# Sheet2.net
KiCad netlist of a schematic drawn in Altium Designer
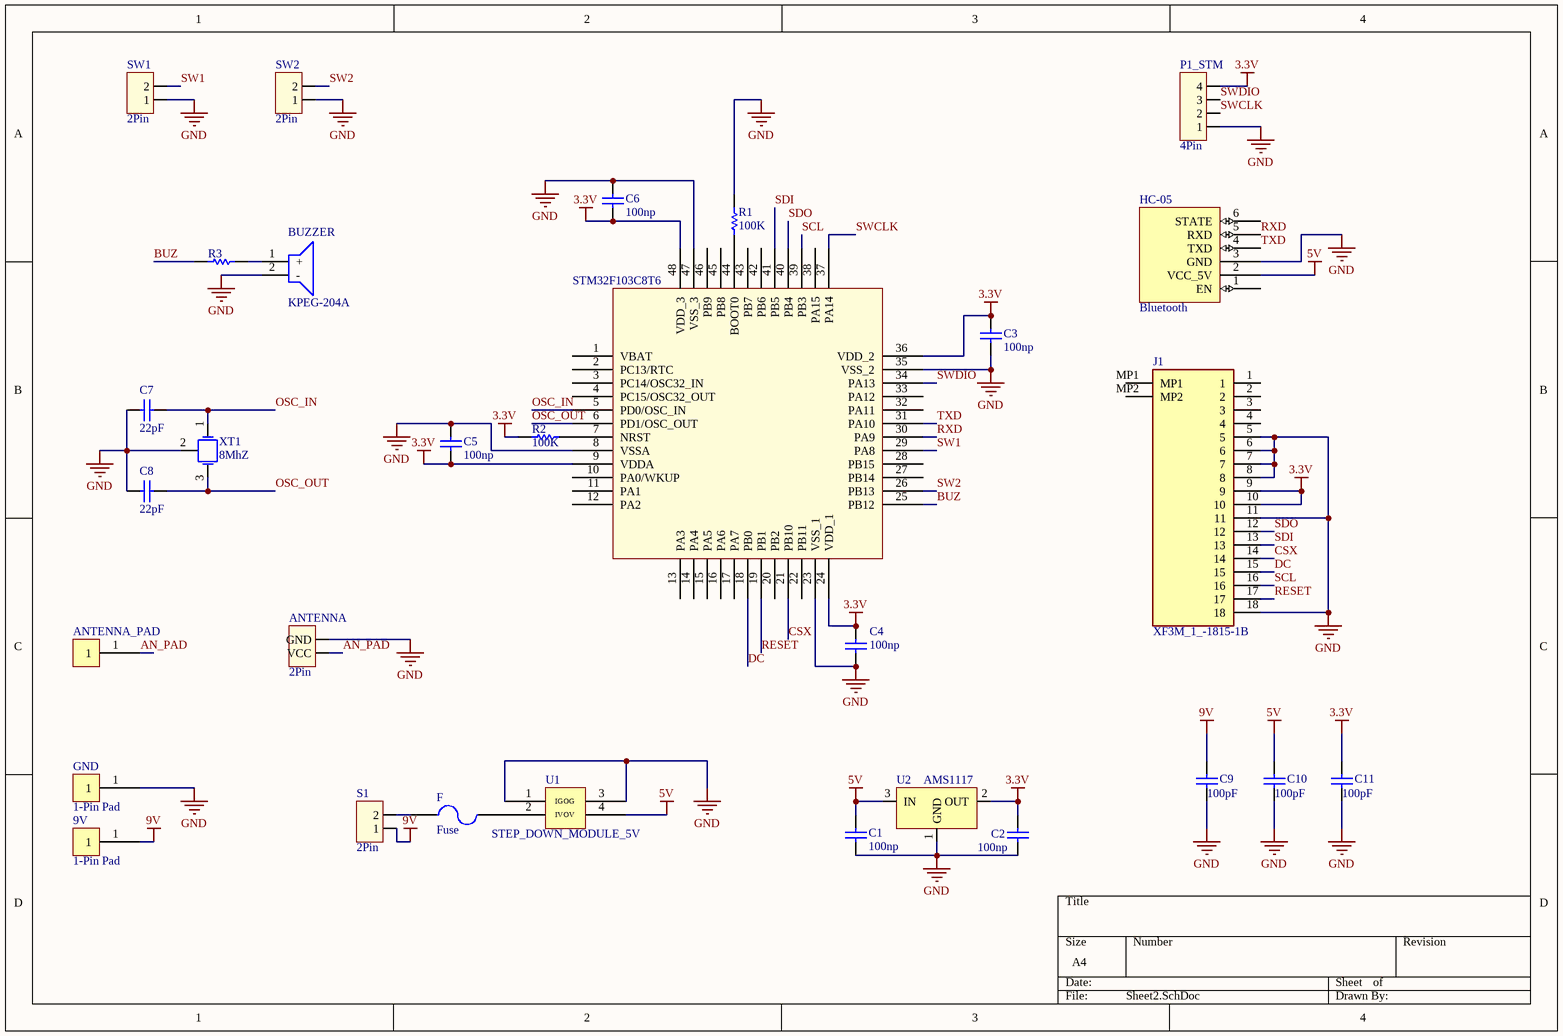
[diagram p0: Sheet2.SchDoc]

(export (version "E")
  (design (tool "Eeschema 10.0.6"))
  (components
    (comp (ref "9V")
      (value "1-Pin Pad")
      (footprint "1-Pin Pad")
      (libsource (lib "Connector") (part "1-Pin Pad"))
    )
    (comp (ref "ANTENNA")
      (value "2Pin")
      (footprint "XH2.54-2pin")
      (libsource (lib "Connector") (part "2Pin"))
    )
    (comp (ref "ANTENNA_PAD")
      (value "1-Pin Pad")
      (footprint "1-Pin Pad")
      (libsource (lib "Connector") (part "1-Pin Pad"))
    )
    (comp (ref "BUZZER")
      (value "KPEG-204A")
      (footprint "SamacSys:KPEG204A")
      (description "Loudspeaker or Buzzer")
      (libsource (lib "*") (part "KPEG-204A"))
    )
    (comp (ref "C1")
      (value "100np")
      (footprint "Passive Comp:C0805")
      (libsource (lib "Passive Comp") (part "Cap"))
    )
    (comp (ref "C2")
      (value "100np")
      (footprint "Passive Comp:C0805")
      (libsource (lib "Passive Comp") (part "Cap"))
    )
    (comp (ref "C3")
      (value "100np")
      (footprint "Passive Comp:C0805")
      (libsource (lib "Passive Comp") (part "Cap"))
    )
    (comp (ref "C4")
      (value "100np")
      (footprint "Passive Comp:C0805")
      (libsource (lib "Passive Comp") (part "Cap"))
    )
    (comp (ref "C5")
      (value "100np")
      (footprint "Passive Comp:C0805")
      (libsource (lib "Passive Comp") (part "Cap"))
    )
    (comp (ref "C6")
      (value "100np")
      (footprint "Passive Comp:C0805")
      (libsource (lib "Passive Comp") (part "Cap"))
    )
    (comp (ref "C7")
      (value "22pF")
      (footprint "Passive Comp:C0805")
      (libsource (lib "Passive Comp") (part "Cap"))
    )
    (comp (ref "C8")
      (value "22pF")
      (footprint "Passive Comp:C0805")
      (libsource (lib "Passive Comp") (part "Cap"))
    )
    (comp (ref "C9")
      (value "100pF")
      (footprint "Passive Comp:C0805")
      (libsource (lib "Passive Comp") (part "Cap"))
    )
    (comp (ref "C10")
      (value "100pF")
      (footprint "Passive Comp:C0805")
      (libsource (lib "Passive Comp") (part "Cap"))
    )
    (comp (ref "C11")
      (value "100pF")
      (footprint "Passive Comp:C0805")
      (libsource (lib "Passive Comp") (part "Cap"))
    )
    (comp (ref "F")
      (value "Fuse")
      (footprint "FUSE-PPTC-30V - 5A")
      (description "PPTC")
      (libsource (lib "Passive Comp") (part "Fuse"))
    )
    (comp (ref "GND")
      (value "1-Pin Pad")
      (footprint "1-Pin Pad")
      (libsource (lib "Connector") (part "1-Pin Pad"))
    )
    (comp (ref "HC-05")
      (value "Bluetooth")
      (footprint "PcbLib1:hc-05")
      (libsource (lib "Schlib1") (part "HC-05"))
    )
    (comp (ref "J1")
      (value "XF3M_1_-1815-1B")
      (footprint "SamacSys:68711814022")
      (description "Connector")
      (fields
        (field (name "MANUFACTURER_PART_NUMBER") "XF3M(1)-1815-1B")
        (field (name "MOUSER PART NUMBER") "653-XF3M1-1815-1B")
      )
      (libsource (lib "SamacSys") (part "XF3M_1_-1815-1B"))
    )
    (comp (ref "P1_STM") (value "4Pin") (footprint "XH2.54-4pin") (libsource (lib "Connector") (part "4Pin")))
    (comp (ref "R1") (value "100K") (footprint "R0805") (libsource (lib "Passive Comp") (part "Resistor_1")))
    (comp (ref "R2") (value "100K") (footprint "R0805") (libsource (lib "Passive Comp") (part "Resistor_1")))
    (comp (ref "R3") (value "1000") (footprint "R0805") (libsource (lib "Passive Comp") (part "Resistor_1")))
    (comp (ref "S1") (value "2Pin") (footprint "XH2.54-2pin") (libsource (lib "Connector") (part "2Pin")))
    (comp (ref "STM")
      (value "STM32F103C8T6")
      (footprint "LQFP48")
      (libsource (lib "STM32") (part "STM32F103C8T6"))
    )
    (comp (ref "SW1") (value "2Pin") (footprint "XH2.54-2pin") (libsource (lib "Connector") (part "2Pin")))
    (comp (ref "SW2") (value "2Pin") (footprint "XH2.54-2pin") (libsource (lib "Connector") (part "2Pin")))
    (comp (ref "U1")
      (value "STEP_DOWN_MODULE_5V")
      (footprint "STEP_DOWN_MODULE_5V")
      (libsource (lib "Schlib1") (part "STEP_DOWN_MODULE_5V"))
    )
    (comp (ref "U2")
      (value "AMS1117")
      (footprint "AMS1117 - SOT-223")
      (libsource (lib "Converter") (part "AMS1117"))
    )
    (comp (ref "XT1")
      (value "8MhZ")
      (footprint "3225-P")
      (libsource (lib "Passive Comp") (part "Passive Crystal"))
    )
  )
  (nets
    (net (code "1") (name "/AN_PAD") (class "Default")
      (node (ref "ANTENNA") (pin "1") (pinfunction "1_1") (pintype "passive"))
      (node (ref "ANTENNA_PAD") (pin "1") (pinfunction "1_1") (pintype "passive"))
    )
    (net (code "2") (name "/BUZ") (class "Default")
      (node (ref "R3") (pin "1") (pinfunction "1_1") (pintype "passive"))
      (node (ref "STM") (pin "25") (pinfunction "PB12_25") (pintype "passive"))
    )
    (net (code "3") (name "/CSX") (class "Default")
      (node (ref "J1") (pin "14") (pinfunction "14_14") (pintype "passive"))
      (node (ref "STM") (pin "21") (pinfunction "PB10_21") (pintype "passive"))
    )
    (net (code "4") (name "/DC") (class "Default")
      (node (ref "J1") (pin "15") (pinfunction "15_15") (pintype "passive"))
      (node (ref "STM") (pin "18") (pinfunction "PB0_18") (pintype "passive"))
    )
    (net (code "5") (name "/OSC_IN") (class "Default")
      (node (ref "C7") (pin "2") (pinfunction "2_2") (pintype "passive"))
      (node (ref "STM") (pin "5") (pinfunction "PD0/OSC_IN_5") (pintype "passive"))
      (node (ref "XT1") (pin "1") (pinfunction "OSC1_1") (pintype "passive"))
    )
    (net (code "6") (name "/OSC_OUT") (class "Default")
      (node (ref "C8") (pin "2") (pinfunction "2_2") (pintype "passive"))
      (node (ref "STM") (pin "6") (pinfunction "PD1/OSC_OUT_6") (pintype "passive"))
      (node (ref "XT1") (pin "3") (pinfunction "OSC2_3") (pintype "passive"))
    )
    (net (code "7") (name "/RESET") (class "Default")
      (node (ref "J1") (pin "17") (pinfunction "17_17") (pintype "passive"))
      (node (ref "STM") (pin "19") (pinfunction "PB1_19") (pintype "passive"))
    )
    (net (code "8") (name "/RXD") (class "Default")
      (node (ref "HC-05") (pin "5") (pinfunction "RXD_5") (pintype "bidirectional"))
      (node (ref "STM") (pin "30") (pinfunction "PA9_30") (pintype "passive"))
    )
    (net (code "9") (name "/SCL") (class "Default")
      (node (ref "J1") (pin "16") (pinfunction "16_16") (pintype "passive"))
      (node (ref "STM") (pin "39") (pinfunction "PB3_39") (pintype "passive"))
    )
    (net (code "10") (name "/SDI") (class "Default")
      (node (ref "J1") (pin "13") (pinfunction "13_13") (pintype "passive"))
      (node (ref "STM") (pin "41") (pinfunction "PB5_41") (pintype "passive"))
    )
    (net (code "11") (name "/SDO") (class "Default")
      (node (ref "J1") (pin "12") (pinfunction "12_12") (pintype "passive"))
      (node (ref "STM") (pin "40") (pinfunction "PB4_40") (pintype "passive"))
    )
    (net (code "12") (name "/SW1") (class "Default")
      (node (ref "STM") (pin "29") (pinfunction "PA8_29") (pintype "passive"))
      (node (ref "SW1") (pin "2") (pinfunction "2_2") (pintype "passive"))
    )
    (net (code "13") (name "/SW2") (class "Default")
      (node (ref "STM") (pin "26") (pinfunction "PB13_26") (pintype "passive"))
      (node (ref "SW2") (pin "2") (pinfunction "2_2") (pintype "passive"))
    )
    (net (code "14") (name "/SWCLK") (class "Default")
      (node (ref "P1_STM") (pin "2") (pinfunction "2_2") (pintype "passive"))
      (node (ref "STM") (pin "37") (pinfunction "PA14_37") (pintype "passive"))
    )
    (net (code "15") (name "/SWDIO") (class "Default")
      (node (ref "P1_STM") (pin "3") (pinfunction "3_3") (pintype "passive"))
      (node (ref "STM") (pin "34") (pinfunction "PA13_34") (pintype "passive"))
    )
    (net (code "16") (name "/TXD") (class "Default")
      (node (ref "HC-05") (pin "4") (pinfunction "TXD_4") (pintype "bidirectional"))
      (node (ref "STM") (pin "31") (pinfunction "PA10_31") (pintype "passive"))
    )
    (net (code "17") (name "3.3V") (class "Default")
      (node (ref "C11") (pin "2") (pinfunction "2_2") (pintype "passive"))
      (node (ref "C2") (pin "2") (pinfunction "2_2") (pintype "passive"))
      (node (ref "C3") (pin "2") (pinfunction "2_2") (pintype "passive"))
      (node (ref "C4") (pin "2") (pinfunction "2_2") (pintype "passive"))
      (node (ref "C5") (pin "1") (pinfunction "1_1") (pintype "passive"))
      (node (ref "C6") (pin "1") (pinfunction "1_1") (pintype "passive"))
      (node (ref "J1") (pin "10") (pinfunction "10_10") (pintype "passive"))
      (node (ref "J1") (pin "9") (pinfunction "9_9") (pintype "passive"))
      (node (ref "P1_STM") (pin "4") (pinfunction "4_4") (pintype "passive"))
      (node (ref "R2") (pin "1") (pinfunction "1_1") (pintype "passive"))
      (node (ref "STM") (pin "24") (pinfunction "VDD_1_24") (pintype "passive"))
      (node (ref "STM") (pin "36") (pinfunction "VDD_2_36") (pintype "passive"))
      (node (ref "STM") (pin "48") (pinfunction "VDD_3_48") (pintype "passive"))
      (node (ref "STM") (pin "9") (pinfunction "VDDA_9") (pintype "passive"))
      (node (ref "U2") (pin "2") (pinfunction "OUT_2") (pintype "passive"))
    )
    (net (code "18") (name "5V") (class "Default")
      (node (ref "C1") (pin "2") (pinfunction "2_2") (pintype "passive"))
      (node (ref "C10") (pin "2") (pinfunction "2_2") (pintype "passive"))
      (node (ref "HC-05") (pin "2") (pinfunction "VCC_5V_2") (pintype "power_in"))
      (node (ref "U1") (pin "4") (pinfunction "OV_4") (pintype "passive"))
      (node (ref "U2") (pin "3") (pinfunction "IN_3") (pintype "passive"))
    )
    (net (code "19") (name "9V") (class "Default")
      (node (ref "9V") (pin "1") (pinfunction "1_1") (pintype "passive"))
      (node (ref "C9") (pin "2") (pinfunction "2_2") (pintype "passive"))
      (node (ref "S1") (pin "1") (pinfunction "1_1") (pintype "passive"))
    )
    (net (code "20") (name "GND") (class "Default")
      (node (ref "ANTENNA") (pin "2") (pinfunction "2_2") (pintype "passive"))
      (node (ref "BUZZER") (pin "2") (pinfunction "-_2") (pintype "passive"))
      (node (ref "C1") (pin "1") (pinfunction "1_1") (pintype "passive"))
      (node (ref "C10") (pin "1") (pinfunction "1_1") (pintype "passive"))
      (node (ref "C11") (pin "1") (pinfunction "1_1") (pintype "passive"))
      (node (ref "C2") (pin "1") (pinfunction "1_1") (pintype "passive"))
      (node (ref "C3") (pin "1") (pinfunction "1_1") (pintype "passive"))
      (node (ref "C4") (pin "1") (pinfunction "1_1") (pintype "passive"))
      (node (ref "C5") (pin "2") (pinfunction "2_2") (pintype "passive"))
      (node (ref "C6") (pin "2") (pinfunction "2_2") (pintype "passive"))
      (node (ref "C7") (pin "1") (pinfunction "1_1") (pintype "passive"))
      (node (ref "C8") (pin "1") (pinfunction "1_1") (pintype "passive"))
      (node (ref "C9") (pin "1") (pinfunction "1_1") (pintype "passive"))
      (node (ref "GND") (pin "1") (pinfunction "1_1") (pintype "passive"))
      (node (ref "HC-05") (pin "3") (pinfunction "GND_3") (pintype "passive"))
      (node (ref "J1") (pin "11") (pinfunction "11_11") (pintype "passive"))
      (node (ref "J1") (pin "18") (pinfunction "18_18") (pintype "passive"))
      (node (ref "J1") (pin "5") (pinfunction "5_5") (pintype "passive"))
      (node (ref "J1") (pin "6") (pinfunction "6_6") (pintype "passive"))
      (node (ref "J1") (pin "7") (pinfunction "7_7") (pintype "passive"))
      (node (ref "J1") (pin "8") (pinfunction "8_8") (pintype "passive"))
      (node (ref "P1_STM") (pin "1") (pinfunction "1_1") (pintype "passive"))
      (node (ref "R1") (pin "2") (pinfunction "2_2") (pintype "passive"))
      (node (ref "STM") (pin "23") (pinfunction "VSS_1_23") (pintype "passive"))
      (node (ref "STM") (pin "35") (pinfunction "VSS_2_35") (pintype "passive"))
      (node (ref "STM") (pin "47") (pinfunction "VSS_3_47") (pintype "passive"))
      (node (ref "STM") (pin "8") (pinfunction "VSSA_8") (pintype "passive"))
      (node (ref "SW1") (pin "1") (pinfunction "1_1") (pintype "passive"))
      (node (ref "SW2") (pin "1") (pinfunction "1_1") (pintype "passive"))
      (node (ref "U1") (pin "1") (pinfunction "IG_1") (pintype "power_in"))
      (node (ref "U1") (pin "3") (pinfunction "OG_3") (pintype "power_in"))
      (node (ref "U2") (pin "1") (pinfunction "GND_1") (pintype "passive"))
      (node (ref "XT1") (pin "2") (pinfunction "2_2") (pintype "passive"))
    )
    (net (code "21") (name "Net-(BUZZER-+)") (class "Default")
      (node (ref "BUZZER") (pin "1") (pinfunction "+_1") (pintype "passive"))
      (node (ref "R3") (pin "2") (pinfunction "2_2") (pintype "passive"))
    )
    (net (code "22") (name "Net-(F-Pad1)") (class "Default")
      (node (ref "F") (pin "1") (pinfunction "1_1") (pintype "passive"))
      (node (ref "S1") (pin "2") (pinfunction "2_2") (pintype "passive"))
    )
    (net (code "23") (name "Net-(STM-BOOT0)") (class "Default")
      (node (ref "R1") (pin "1") (pinfunction "1_1") (pintype "passive"))
      (node (ref "STM") (pin "44") (pinfunction "BOOT0_44") (pintype "passive"))
    )
    (net (code "24") (name "Net-(STM-NRST)") (class "Default")
      (node (ref "R2") (pin "2") (pinfunction "2_2") (pintype "passive"))
      (node (ref "STM") (pin "7") (pinfunction "NRST_7") (pintype "passive"))
    )
    (net (code "25") (name "Net-(U1-IV)") (class "Default")
      (node (ref "F") (pin "2") (pinfunction "2_2") (pintype "passive"))
      (node (ref "U1") (pin "2") (pinfunction "IV_2") (pintype "passive"))
    )
    (net (code "26") (name "unconnected-(HC-05-EN-Pad1)") (class "Default")
      (node (ref "HC-05") (pin "1") (pinfunction "EN_1") (pintype "bidirectional"))
    )
    (net (code "27") (name "unconnected-(HC-05-STATE-Pad6)") (class "Default")
      (node (ref "HC-05") (pin "6") (pinfunction "STATE_6") (pintype "bidirectional"))
    )
    (net (code "28") (name "unconnected-(J1-Pad1)") (class "Default")
      (node (ref "J1") (pin "1") (pinfunction "1_1") (pintype "passive"))
    )
    (net (code "29") (name "unconnected-(J1-Pad2)") (class "Default")
      (node (ref "J1") (pin "2") (pinfunction "2_2") (pintype "passive"))
    )
    (net (code "30") (name "unconnected-(J1-Pad3)") (class "Default")
      (node (ref "J1") (pin "3") (pinfunction "3_3") (pintype "passive"))
    )
    (net (code "31") (name "unconnected-(J1-Pad4)") (class "Default")
      (node (ref "J1") (pin "4") (pinfunction "4_4") (pintype "passive"))
    )
    (net (code "32") (name "unconnected-(J1-PadMP1)") (class "Default")
      (node (ref "J1") (pin "MP1") (pinfunction "MP1_MP1") (pintype "passive"))
    )
    (net (code "33") (name "unconnected-(J1-PadMP2)") (class "Default")
      (node (ref "J1") (pin "MP2") (pinfunction "MP2_MP2") (pintype "passive"))
    )
    (net (code "34") (name "unconnected-(STM-PA0{slash}WKUP-Pad10)") (class "Default")
      (node (ref "STM") (pin "10") (pinfunction "PA0/WKUP_10") (pintype "passive"))
    )
    (net (code "35") (name "unconnected-(STM-PA1-Pad11)") (class "Default")
      (node (ref "STM") (pin "11") (pinfunction "PA1_11") (pintype "passive"))
    )
    (net (code "36") (name "unconnected-(STM-PA2-Pad12)") (class "Default")
      (node (ref "STM") (pin "12") (pinfunction "PA2_12") (pintype "passive"))
    )
    (net (code "37") (name "unconnected-(STM-PA3-Pad13)") (class "Default")
      (node (ref "STM") (pin "13") (pinfunction "PA3_13") (pintype "passive"))
    )
    (net (code "38") (name "unconnected-(STM-PA4-Pad14)") (class "Default")
      (node (ref "STM") (pin "14") (pinfunction "PA4_14") (pintype "passive"))
    )
    (net (code "39") (name "unconnected-(STM-PA5-Pad15)") (class "Default")
      (node (ref "STM") (pin "15") (pinfunction "PA5_15") (pintype "passive"))
    )
    (net (code "40") (name "unconnected-(STM-PA6-Pad16)") (class "Default")
      (node (ref "STM") (pin "16") (pinfunction "PA6_16") (pintype "passive"))
    )
    (net (code "41") (name "unconnected-(STM-PA7-Pad17)") (class "Default")
      (node (ref "STM") (pin "17") (pinfunction "PA7_17") (pintype "passive"))
    )
    (net (code "42") (name "unconnected-(STM-PA11-Pad32)") (class "Default")
      (node (ref "STM") (pin "32") (pinfunction "PA11_32") (pintype "passive"))
    )
    (net (code "43") (name "unconnected-(STM-PA12-Pad33)") (class "Default")
      (node (ref "STM") (pin "33") (pinfunction "PA12_33") (pintype "passive"))
    )
    (net (code "44") (name "unconnected-(STM-PA15-Pad38)") (class "Default")
      (node (ref "STM") (pin "38") (pinfunction "PA15_38") (pintype "passive"))
    )
    (net (code "45") (name "unconnected-(STM-PB2-Pad20)") (class "Default")
      (node (ref "STM") (pin "20") (pinfunction "PB2_20") (pintype "passive"))
    )
    (net (code "46") (name "unconnected-(STM-PB6-Pad42)") (class "Default")
      (node (ref "STM") (pin "42") (pinfunction "PB6_42") (pintype "passive"))
    )
    (net (code "47") (name "unconnected-(STM-PB7-Pad43)") (class "Default")
      (node (ref "STM") (pin "43") (pinfunction "PB7_43") (pintype "passive"))
    )
    (net (code "48") (name "unconnected-(STM-PB8-Pad45)") (class "Default")
      (node (ref "STM") (pin "45") (pinfunction "PB8_45") (pintype "passive"))
    )
    (net (code "49") (name "unconnected-(STM-PB9-Pad46)") (class "Default")
      (node (ref "STM") (pin "46") (pinfunction "PB9_46") (pintype "passive"))
    )
    (net (code "50") (name "unconnected-(STM-PB11-Pad22)") (class "Default")
      (node (ref "STM") (pin "22") (pinfunction "PB11_22") (pintype "passive"))
    )
    (net (code "51") (name "unconnected-(STM-PB14-Pad27)") (class "Default")
      (node (ref "STM") (pin "27") (pinfunction "PB14_27") (pintype "passive"))
    )
    (net (code "52") (name "unconnected-(STM-PB15-Pad28)") (class "Default")
      (node (ref "STM") (pin "28") (pinfunction "PB15_28") (pintype "passive"))
    )
    (net (code "53") (name "unconnected-(STM-PC13{slash}RTC-Pad2)") (class "Default")
      (node (ref "STM") (pin "2") (pinfunction "PC13/RTC_2") (pintype "passive"))
    )
    (net (code "54") (name "unconnected-(STM-PC14{slash}OSC32_IN-Pad3)") (class "Default")
      (node (ref "STM") (pin "3") (pinfunction "PC14/OSC32_IN_3") (pintype "passive"))
    )
    (net (code "55") (name "unconnected-(STM-PC15{slash}OSC32_OUT-Pad4)") (class "Default")
      (node (ref "STM") (pin "4") (pinfunction "PC15/OSC32_OUT_4") (pintype "passive"))
    )
    (net (code "56") (name "unconnected-(STM-VBAT-Pad1)") (class "Default")
      (node (ref "STM") (pin "1") (pinfunction "VBAT_1") (pintype "passive"))
    )
  )
)
